# RelayModule_LED.net
KiCad netlist of a schematic drawn in Altium Designer
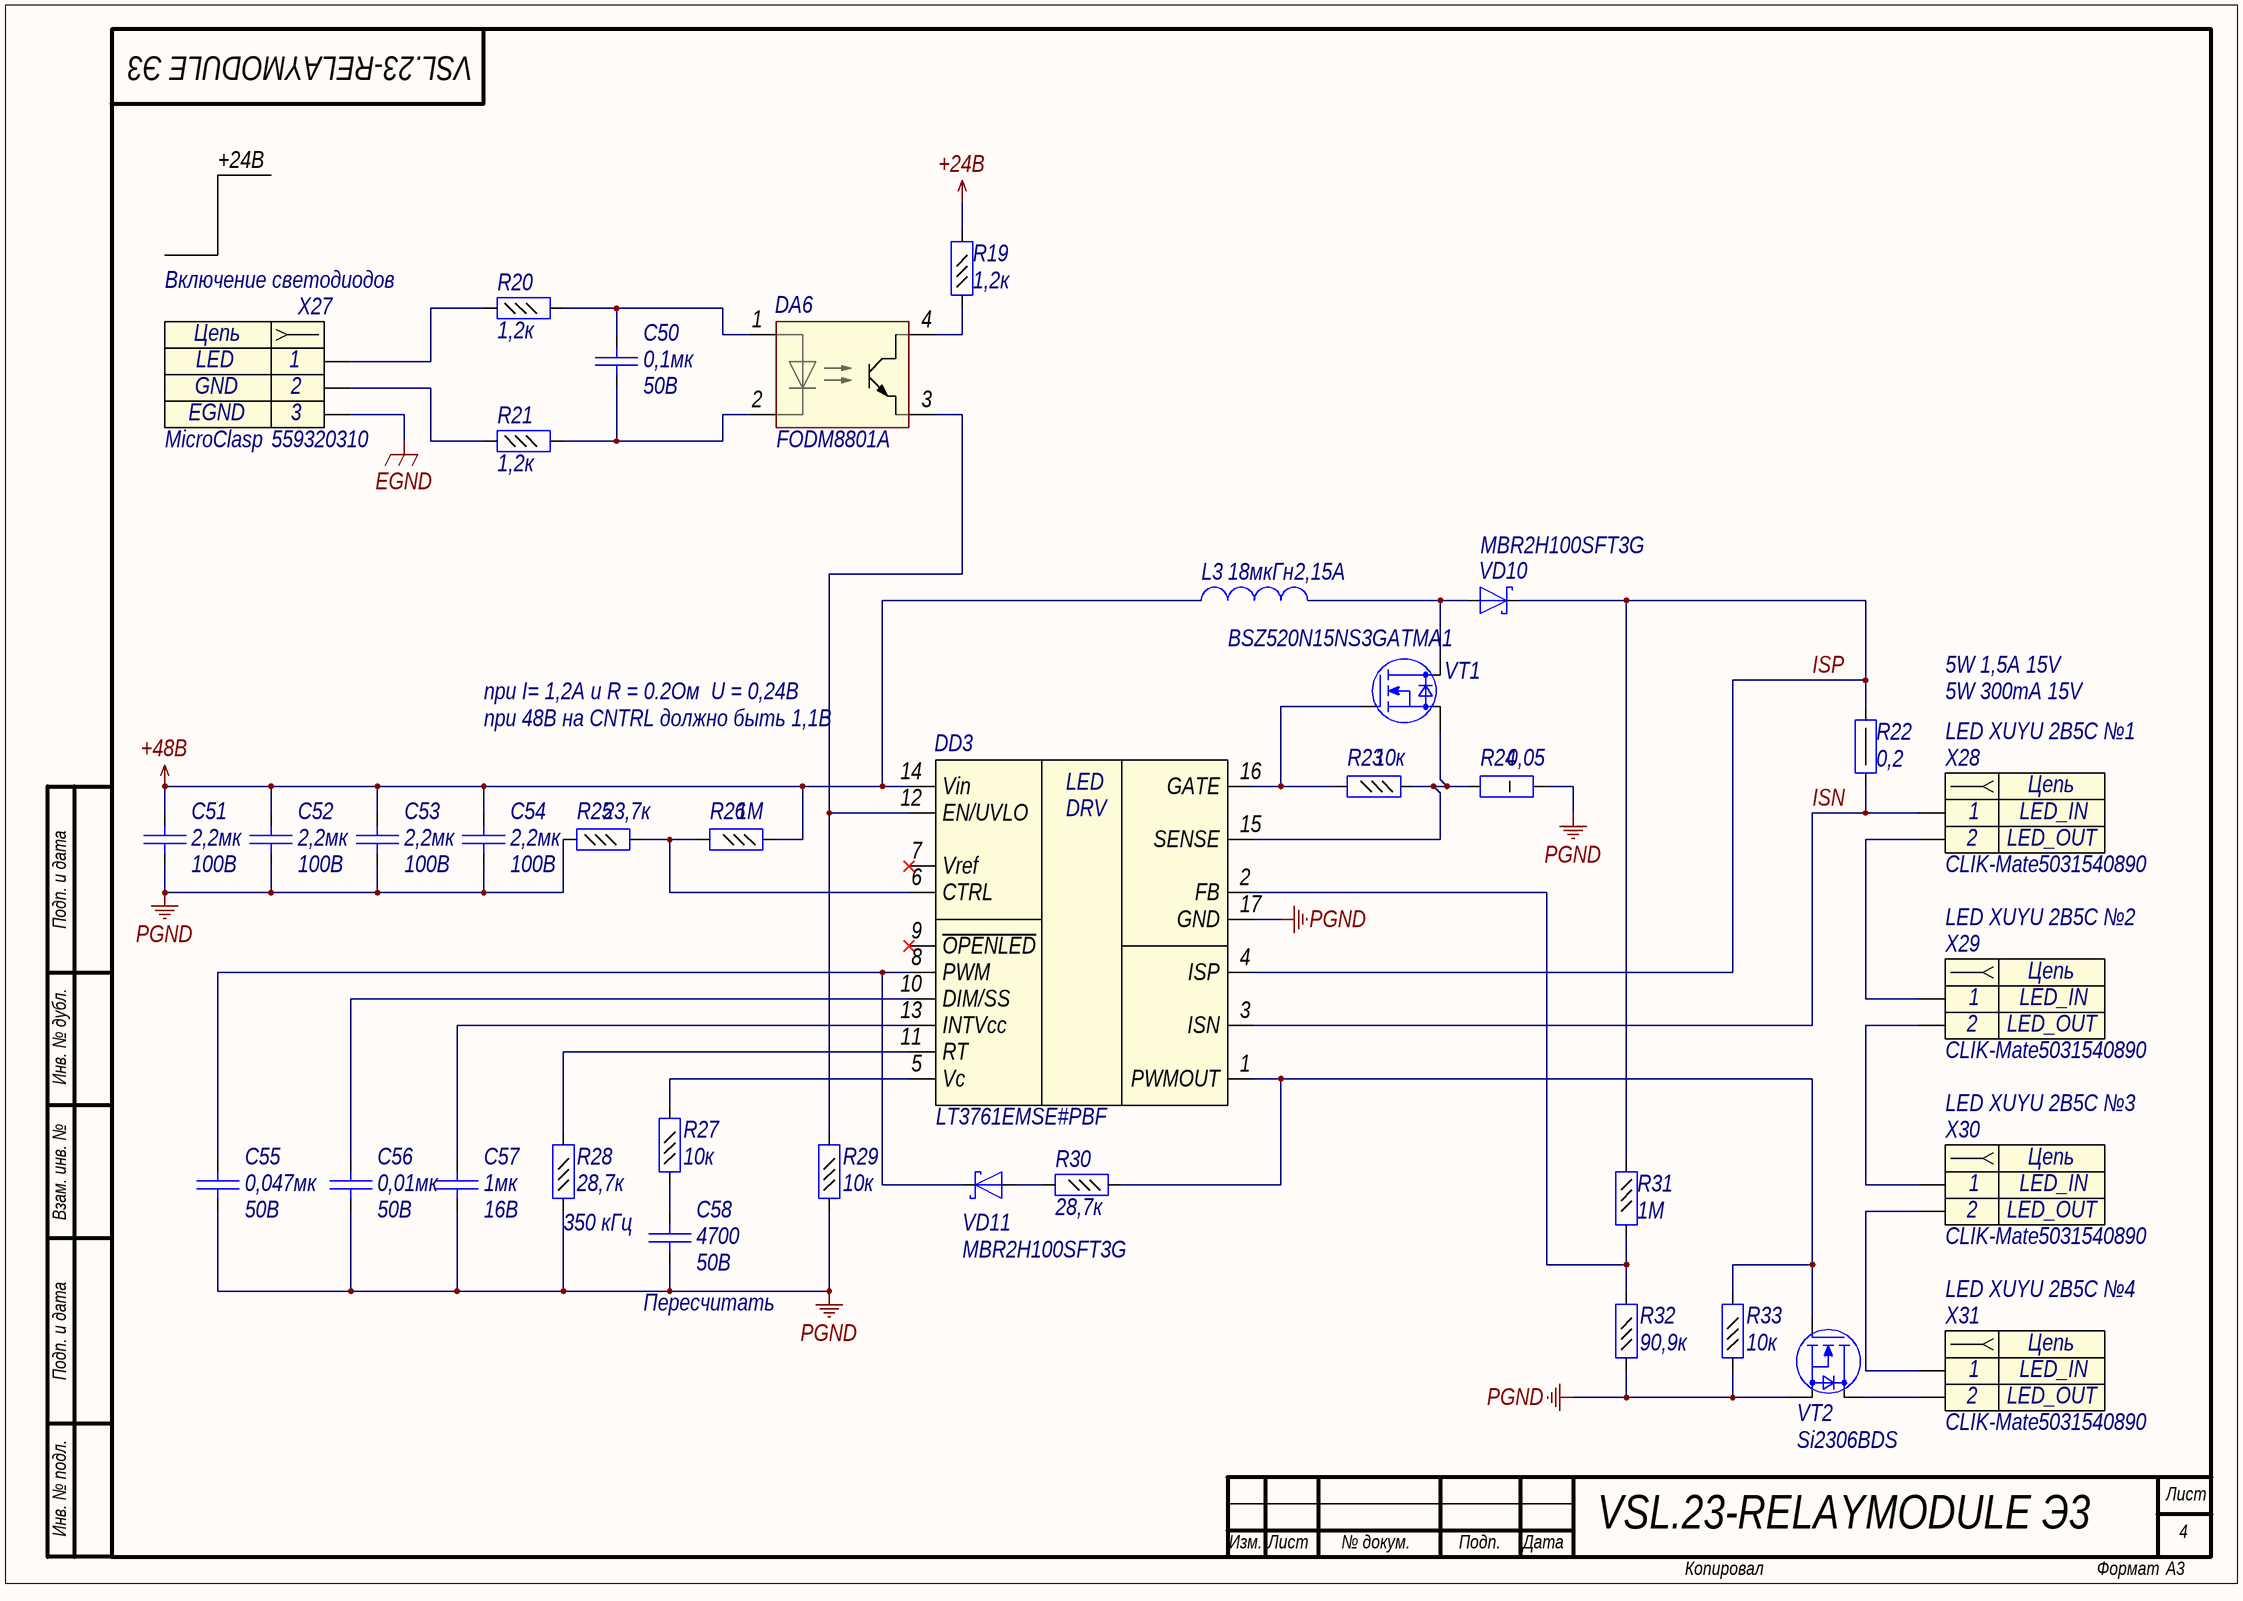
[diagram p0: RelayModule_LED.SchDoc]

(export (version "E")
  (design (tool "Eeschema 10.0.6"))
  (components
    (comp (ref "C50")
      (value "0,1мк")
      (footprint "C0402")
      (description "Конденсатор")
      (fields (field (name "VOLTAGE") "50В") (field (name "PART NUMBER") "GRM155R71H104KE14D "))
      (libsource (lib "MOP44") (part "Capacitor"))
    )
    (comp (ref "C51")
      (value "2,2мк")
      (footprint "C1812")
      (description "Конденсатор")
      (fields (field (name "VOLTAGE") "100В") (field (name "PART NUMBER") "C4532X7R2A225M"))
      (libsource (lib "MOP44") (part "Capacitor"))
    )
    (comp (ref "C52")
      (value "2,2мк")
      (footprint "C1812")
      (description "Конденсатор")
      (fields (field (name "VOLTAGE") "100В") (field (name "PART NUMBER") "C4532X7R2A225M"))
      (libsource (lib "MOP44") (part "Capacitor"))
    )
    (comp (ref "C53")
      (value "2,2мк")
      (footprint "C1812")
      (description "Конденсатор")
      (fields (field (name "VOLTAGE") "100В") (field (name "PART NUMBER") "C4532X7R2A225M"))
      (libsource (lib "MOP44") (part "Capacitor"))
    )
    (comp (ref "C54")
      (value "2,2мк")
      (footprint "C1812")
      (description "Конденсатор")
      (fields (field (name "VOLTAGE") "100В") (field (name "PART NUMBER") "C4532X7R2A225M"))
      (libsource (lib "MOP44") (part "Capacitor"))
    )
    (comp (ref "C55")
      (value "0,047мк")
      (footprint "C0402")
      (description "Конденсатор")
      (fields (field (name "VOLTAGE") "50В") (field (name "PART NUMBER") "CC0402KRX7R9BB473"))
      (libsource (lib "MOP44") (part "Capacitor"))
    )
    (comp (ref "C56")
      (value "0,01мк")
      (footprint "C0402")
      (description "Конденсатор")
      (fields (field (name "VOLTAGE") "50B") (field (name "PART NUMBER") "GRM155R71H103K"))
      (libsource (lib "MOP44") (part "Capacitor"))
    )
    (comp (ref "C57")
      (value "1мк")
      (footprint "C0603")
      (description "Конденсатор")
      (fields
        (field (name "VOLTAGE") "16B")
        (field (name "PART NUMBER") "GRM188R71C105KA12D**")
        (field (name "Comment") "Capacitor")
      )
      (libsource (lib "MOP44") (part "Capacitor"))
    )
    (comp (ref "C58")
      (value "4700")
      (footprint "C0402")
      (description "Конденсатор")
      (fields (field (name "VOLTAGE") "50B") (field (name "PART NUMBER") "GRM155R71H472K"))
      (libsource (lib "MOP44") (part "Capacitor"))
    )
    (comp (ref "DA6")
      (value "OPTO-1")
      (footprint "Miniflat4")
      (description "Опторазвязка")
      (fields (field (name "PART NUMBER") "FODM8801A") (field (name "MANUFACTURER") "ON Semiconductor"))
      (libsource (lib "MOP44") (part "OPTO-1"))
    )
    (comp (ref "DD3")
      (value "LT3761")
      (footprint "MSOP16")
      (description "LED Controller with  Internal PWM Generato")
      (fields (field (name "PART NUMBER") "LT3761EMSE#PBF"))
      (libsource (lib "MOP44") (part "LT3761"))
    )
    (comp (ref "L3")
      (value "18мкГн")
      (footprint "SDR1006")
      (description "EMI Suppression Filter")
      (fields
        (field (name "RATED CURRENT") "2,15A")
        (field (name "PART NUMBER") "SDR1006- 180ML")
        (field (name "Comment") "Inductor")
      )
      (libsource (lib "MOP44") (part "Inductor"))
    )
    (comp (ref "R19")
      (value "1,2к")
      (footprint "R0402")
      (description "Резистор")
      (fields (field (name "PART NUMBER") "RC0402FR-071K2") (field (name "POWER") "0,062Вт"))
      (libsource (lib "") (part "Resistor_0,062Вт_1"))
    )
    (comp (ref "R20")
      (value "1,2к")
      (footprint "R0402")
      (description "Резистор")
      (fields (field (name "PART NUMBER") "RC0402FR-071K2") (field (name "POWER") "0,062Вт"))
      (libsource (lib "") (part "Resistor_0,062Вт_3"))
    )
    (comp (ref "R21")
      (value "1,2к")
      (footprint "R0402")
      (description "Резистор")
      (fields (field (name "PART NUMBER") "RC0402FR-071K2") (field (name "POWER") "0,062Вт"))
      (libsource (lib "") (part "Resistor_0,062Вт_3"))
    )
    (comp (ref "R22")
      (value "0,2")
      (footprint "R1210")
      (description "Резистор")
      (fields (field (name "PART NUMBER") "RL1210FR-070R2L") (field (name "POWER") "0,5Вт"))
      (libsource (lib "MOP44") (part "Resistor_0,5Вт"))
    )
    (comp (ref "R23")
      (value "10к")
      (footprint "R0402")
      (description "Резистор")
      (fields (field (name "PART NUMBER") "RC0402FR-0710KL") (field (name "POWER") "0,062Вт"))
      (libsource (lib "") (part "Resistor_0,062Вт_2"))
    )
    (comp (ref "R24")
      (value "0,05")
      (footprint "R2010")
      (description "Резистор")
      (fields (field (name "PART NUMBER") "RL2010FK-070R05L") (field (name "POWER") "0,75Вт"))
      (libsource (lib "MOP44") (part "Resistor_1Вт"))
    )
    (comp (ref "R25")
      (value "23,7к")
      (footprint "R0402")
      (description "Резистор")
      (fields (field (name "PART NUMBER") "RC0402FR-0723K7L") (field (name "POWER") "0,062Вт"))
      (libsource (lib "") (part "Resistor_0,062Вт_3"))
    )
    (comp (ref "R26")
      (value "1М")
      (footprint "R0402")
      (description "Резистор")
      (fields (field (name "PART NUMBER") "RC0402FR-071ML") (field (name "POWER") "0,062Вт"))
      (libsource (lib "") (part "Resistor_0,062Вт_2"))
    )
    (comp (ref "R27")
      (value "10к")
      (footprint "R0402")
      (description "Резистор")
      (fields (field (name "PART NUMBER") "RC0402FR-0710KL") (field (name "POWER") "0,062Вт"))
      (libsource (lib "") (part "Resistor_0,062Вт_1"))
    )
    (comp (ref "R28")
      (value "28,7к")
      (footprint "R0402")
      (description "Резистор")
      (fields (field (name "PART NUMBER") "RC0402FR-0728K7L") (field (name "POWER") "0,062Вт"))
      (libsource (lib "") (part "Resistor_0,062Вт_1"))
    )
    (comp (ref "R29")
      (value "10к")
      (footprint "R0402")
      (description "Резистор")
      (fields (field (name "PART NUMBER") "RC0402FR-0710KL") (field (name "POWER") "0,062Вт"))
      (libsource (lib "") (part "Resistor_0,062Вт_1"))
    )
    (comp (ref "R30")
      (value "28,7к")
      (footprint "R0402")
      (description "Резистор")
      (fields (field (name "PART NUMBER") "RC0402FR-0728K7L") (field (name "POWER") "0,062Вт"))
      (libsource (lib "") (part "Resistor_0,062Вт_2"))
    )
    (comp (ref "R31")
      (value "1М")
      (footprint "R0402")
      (description "Резистор")
      (fields (field (name "PART NUMBER") "RC0402FR-071ML") (field (name "POWER") "0,062Вт"))
      (libsource (lib "MOP44") (part "Resistor_0,062Вт"))
    )
    (comp (ref "R32")
      (value "90,9к")
      (footprint "R0402")
      (description "Резистор")
      (fields (field (name "PART NUMBER") "RC0402FR-0790K9L") (field (name "POWER") "0,062Вт"))
      (libsource (lib "") (part "Resistor_0,062Вт_1"))
    )
    (comp (ref "R33")
      (value "10к")
      (footprint "R0402")
      (description "Резистор")
      (fields (field (name "PART NUMBER") "RC0402FR-0710KL") (field (name "POWER") "0,062Вт"))
      (libsource (lib "") (part "Resistor_0,062Вт_1"))
    )
    (comp (ref "VD10")
      (value "DiodeSchottky")
      (footprint "SOD-123")
      (description "Диод Шоттки")
      (fields (field (name "PART NUMBER") "MBR2H100SFT3G"))
      (libsource (lib "MOP44") (part "DiodeSchottky"))
    )
    (comp (ref "VD11")
      (value "DiodeSchottky")
      (footprint "SOD-123")
      (description "Диод Шоттки")
      (fields (field (name "PART NUMBER") "MBR2H100SFT3G"))
      (libsource (lib "MOP44") (part "DiodeSchottky"))
    )
    (comp (ref "VT1")
      (value "N-MOSFET")
      (footprint "TSDSON8")
      (fields
        (field (name "PART NUMBER") "BSZ520N15NS3GATMA1")
        (field (name "MANUFACTURER") "Infineon Technologies")
      )
      (libsource (lib "MOP44") (part "N-MOSFET"))
    )
    (comp (ref "VT2")
      (value "N-MOSFET")
      (footprint "SOT23-3")
      (fields (field (name "PART NUMBER") "Si2306BDS") (field (name "MANUFACTURER") "Vishay"))
      (libsource (lib "MOP44") (part "N-MOSFET"))
    )
    (comp (ref "X27")
      (value "Включение светодиодов")
      (footprint "MOLEX_559320310")
      (description "Разъем - 3 конт. розетка")
      (fields (field (name "PART NAME") "MicroClasp") (field (name "PART NUMBER") "559320310"))
      (libsource (lib "MOP44") (part "Header_3_sct"))
    )
    (comp (ref "X28")
      (value "LED XUYU 2B5C №1")
      (footprint "MOLEX_5031540890")
      (description "Разъем - 2 конт. розетка")
      (fields (field (name "PART NAME") "CLIK-Mate") (field (name "PART NUMBER") "5031540890"))
      (libsource (lib "MOP44") (part "Header_2_sct"))
    )
    (comp (ref "X29")
      (value "LED XUYU 2B5C №2")
      (footprint "MOLEX_5031540890")
      (description "Разъем - 2 конт. розетка")
      (fields (field (name "PART NAME") "CLIK-Mate") (field (name "PART NUMBER") "5031540890"))
      (libsource (lib "MOP44") (part "Header_2_sct"))
    )
    (comp (ref "X30")
      (value "LED XUYU 2B5C №3")
      (footprint "MOLEX_5031540890")
      (description "Разъем - 2 конт. розетка")
      (fields (field (name "PART NAME") "CLIK-Mate") (field (name "PART NUMBER") "5031540890"))
      (libsource (lib "MOP44") (part "Header_2_sct"))
    )
    (comp (ref "X31")
      (value "LED XUYU 2B5C №4")
      (footprint "MOLEX_5031540890")
      (description "Разъем - 2 конт. розетка")
      (fields (field (name "PART NAME") "CLIK-Mate") (field (name "PART NUMBER") "5031540890"))
      (libsource (lib "MOP44") (part "Header_2_sct"))
    )
  )
  (nets
    (net (code "1") (name "+24B") (class "Default")
      (node (ref "R19") (pin "2") (pinfunction "2_2") (pintype "passive"))
    )
    (net (code "2") (name "+48B") (class "Default")
      (node (ref "C51") (pin "2") (pinfunction "2_2") (pintype "passive"))
      (node (ref "C52") (pin "2") (pinfunction "2_2") (pintype "passive"))
      (node (ref "C53") (pin "2") (pinfunction "2_2") (pintype "passive"))
      (node (ref "C54") (pin "2") (pinfunction "2_2") (pintype "passive"))
      (node (ref "DD3") (pin "14") (pinfunction "Vin_14") (pintype "passive"))
      (node (ref "L3") (pin "1") (pinfunction "1_1") (pintype "passive"))
      (node (ref "R26") (pin "1") (pinfunction "1_1") (pintype "passive"))
    )
    (net (code "3") (name "/ISN") (class "Default")
      (node (ref "DD3") (pin "3") (pinfunction "ISN_3") (pintype "passive"))
      (node (ref "R22") (pin "2") (pinfunction "2_2") (pintype "passive"))
      (node (ref "X28") (pin "1") (pinfunction "1_1") (pintype "passive"))
    )
    (net (code "4") (name "/ISP") (class "Default")
      (node (ref "DD3") (pin "4") (pinfunction "ISP_4") (pintype "passive"))
      (node (ref "R22") (pin "1") (pinfunction "1_1") (pintype "passive"))
      (node (ref "R31") (pin "1") (pinfunction "1_1") (pintype "passive"))
      (node (ref "VD10") (pin "1") (pinfunction "K_1") (pintype "passive"))
    )
    (net (code "5") (name "EGND") (class "Default")
      (node (ref "X27") (pin "3") (pinfunction "3_3") (pintype "passive"))
    )
    (net (code "6") (name "Net-(C50-Pad1)") (class "Default")
      (node (ref "C50") (pin "1") (pinfunction "1_1") (pintype "passive"))
      (node (ref "DA6") (pin "2") (pintype "passive"))
      (node (ref "R21") (pin "2") (pinfunction "2_2") (pintype "passive"))
    )
    (net (code "7") (name "Net-(C50-Pad2)") (class "Default")
      (node (ref "C50") (pin "2") (pinfunction "2_2") (pintype "passive"))
      (node (ref "DA6") (pin "1") (pintype "passive"))
      (node (ref "R20") (pin "2") (pinfunction "2_2") (pintype "passive"))
    )
    (net (code "8") (name "Net-(C58-Pad2)") (class "Default")
      (node (ref "C58") (pin "2") (pinfunction "2_2") (pintype "passive"))
      (node (ref "R27") (pin "1") (pinfunction "1_1") (pintype "passive"))
    )
    (net (code "9") (name "Net-(DA6-Pad4)") (class "Default")
      (node (ref "DA6") (pin "4") (pintype "passive"))
      (node (ref "R19") (pin "1") (pinfunction "1_1") (pintype "passive"))
    )
    (net (code "10") (name "Net-(DD3-CTRL)") (class "Default")
      (node (ref "DD3") (pin "6") (pinfunction "CTRL_6") (pintype "passive"))
      (node (ref "R25") (pin "2") (pinfunction "2_2") (pintype "passive"))
      (node (ref "R26") (pin "2") (pinfunction "2_2") (pintype "passive"))
    )
    (net (code "11") (name "Net-(DD3-DIM{slash}SS)") (class "Default")
      (node (ref "C56") (pin "2") (pinfunction "2_2") (pintype "passive"))
      (node (ref "DD3") (pin "10") (pinfunction "DIM/SS_10") (pintype "passive"))
    )
    (net (code "12") (name "Net-(DD3-EN{slash}UVLO)") (class "Default")
      (node (ref "DA6") (pin "3") (pintype "passive"))
      (node (ref "DD3") (pin "12") (pinfunction "EN/UVLO_12") (pintype "passive"))
      (node (ref "R29") (pin "2") (pinfunction "2_2") (pintype "passive"))
    )
    (net (code "13") (name "Net-(DD3-FB)") (class "Default")
      (node (ref "DD3") (pin "2") (pinfunction "FB_2") (pintype "passive"))
      (node (ref "R31") (pin "2") (pinfunction "2_2") (pintype "passive"))
      (node (ref "R32") (pin "2") (pinfunction "2_2") (pintype "passive"))
    )
    (net (code "14") (name "Net-(DD3-GATE)") (class "Default")
      (node (ref "DD3") (pin "16") (pinfunction "GATE_16") (pintype "passive"))
      (node (ref "R23") (pin "2") (pinfunction "2_2") (pintype "passive"))
      (node (ref "VT1") (pin "1") (pinfunction "G_1") (pintype "passive"))
    )
    (net (code "15") (name "Net-(DD3-INTVcc)") (class "Default")
      (node (ref "C57") (pin "2") (pinfunction "2_2") (pintype "passive"))
      (node (ref "DD3") (pin "13") (pinfunction "INTVcc_13") (pintype "passive"))
    )
    (net (code "16") (name "Net-(DD3-PWM)") (class "Default")
      (node (ref "C55") (pin "2") (pinfunction "2_2") (pintype "passive"))
      (node (ref "DD3") (pin "8") (pinfunction "PWM_8") (pintype "passive"))
      (node (ref "VD11") (pin "1") (pinfunction "K_1") (pintype "passive"))
    )
    (net (code "17") (name "Net-(DD3-PWMOUT)") (class "Default")
      (node (ref "DD3") (pin "1") (pinfunction "PWMOUT_1") (pintype "passive"))
      (node (ref "R30") (pin "1") (pinfunction "1_1") (pintype "passive"))
      (node (ref "R33") (pin "2") (pinfunction "2_2") (pintype "passive"))
      (node (ref "VT2") (pin "1") (pinfunction "G_1") (pintype "passive"))
    )
    (net (code "18") (name "Net-(DD3-RT)") (class "Default")
      (node (ref "DD3") (pin "11") (pinfunction "RT_11") (pintype "passive"))
      (node (ref "R28") (pin "2") (pinfunction "2_2") (pintype "passive"))
    )
    (net (code "19") (name "Net-(DD3-SENSE)") (class "Default")
      (node (ref "DD3") (pin "15") (pinfunction "SENSE_15") (pintype "passive"))
      (node (ref "R23") (pin "1") (pinfunction "1_1") (pintype "passive"))
      (node (ref "R24") (pin "1") (pinfunction "1_1") (pintype "passive"))
      (node (ref "VT1") (pin "3") (pinfunction "S_3") (pintype "passive"))
    )
    (net (code "20") (name "Net-(DD3-Vc)") (class "Default")
      (node (ref "DD3") (pin "5") (pinfunction "Vc_5") (pintype "passive"))
      (node (ref "R27") (pin "2") (pinfunction "2_2") (pintype "passive"))
    )
    (net (code "21") (name "Net-(R20-Pad1)") (class "Default")
      (node (ref "R20") (pin "1") (pinfunction "1_1") (pintype "passive"))
      (node (ref "X27") (pin "1") (pinfunction "1_1") (pintype "passive"))
    )
    (net (code "22") (name "Net-(R21-Pad1)") (class "Default")
      (node (ref "R21") (pin "1") (pinfunction "1_1") (pintype "passive"))
      (node (ref "X27") (pin "2") (pinfunction "2_2") (pintype "passive"))
    )
    (net (code "23") (name "Net-(VD10-A)") (class "Default")
      (node (ref "L3") (pin "2") (pinfunction "2_2") (pintype "passive"))
      (node (ref "VD10") (pin "2") (pinfunction "A_2") (pintype "passive"))
      (node (ref "VT1") (pin "2") (pinfunction "D_2") (pintype "passive"))
    )
    (net (code "24") (name "Net-(VD11-A)") (class "Default")
      (node (ref "R30") (pin "2") (pinfunction "2_2") (pintype "passive"))
      (node (ref "VD11") (pin "2") (pinfunction "A_2") (pintype "passive"))
    )
    (net (code "25") (name "Net-(VT2-D)") (class "Default")
      (node (ref "VT2") (pin "2") (pinfunction "D_2") (pintype "passive"))
      (node (ref "X31") (pin "2") (pinfunction "2_2") (pintype "passive"))
    )
    (net (code "26") (name "Net-(X28-Pad2)") (class "Default")
      (node (ref "X28") (pin "2") (pinfunction "2_2") (pintype "passive"))
      (node (ref "X29") (pin "1") (pinfunction "1_1") (pintype "passive"))
    )
    (net (code "27") (name "Net-(X29-Pad2)") (class "Default")
      (node (ref "X29") (pin "2") (pinfunction "2_2") (pintype "passive"))
      (node (ref "X30") (pin "1") (pinfunction "1_1") (pintype "passive"))
    )
    (net (code "28") (name "Net-(X30-Pad2)") (class "Default")
      (node (ref "X30") (pin "2") (pinfunction "2_2") (pintype "passive"))
      (node (ref "X31") (pin "1") (pinfunction "1_1") (pintype "passive"))
    )
    (net (code "29") (name "PGND") (class "Default")
      (node (ref "C51") (pin "1") (pinfunction "1_1") (pintype "passive"))
      (node (ref "C52") (pin "1") (pinfunction "1_1") (pintype "passive"))
      (node (ref "C53") (pin "1") (pinfunction "1_1") (pintype "passive"))
      (node (ref "C54") (pin "1") (pinfunction "1_1") (pintype "passive"))
      (node (ref "C55") (pin "1") (pinfunction "1_1") (pintype "passive"))
      (node (ref "C56") (pin "1") (pinfunction "1_1") (pintype "passive"))
      (node (ref "C57") (pin "1") (pinfunction "1_1") (pintype "passive"))
      (node (ref "C58") (pin "1") (pinfunction "1_1") (pintype "passive"))
      (node (ref "DD3") (pin "17") (pinfunction "GND_17") (pintype "passive"))
      (node (ref "R24") (pin "2") (pinfunction "5_2") (pintype "passive"))
      (node (ref "R25") (pin "1") (pinfunction "1_1") (pintype "passive"))
      (node (ref "R28") (pin "1") (pinfunction "1_1") (pintype "passive"))
      (node (ref "R29") (pin "1") (pinfunction "1_1") (pintype "passive"))
      (node (ref "R32") (pin "1") (pinfunction "1_1") (pintype "passive"))
      (node (ref "R33") (pin "1") (pinfunction "1_1") (pintype "passive"))
      (node (ref "VT2") (pin "3") (pinfunction "S_3") (pintype "passive"))
    )
    (net (code "30") (name "unconnected-(DD3-Vref-Pad7)") (class "Default")
      (node (ref "DD3") (pin "7") (pinfunction "Vref_7") (pintype "passive+no_connect"))
    )
    (net (code "31") (name "unconnected-(DD3-~{OPENLED}-Pad9)") (class "Default")
      (node (ref "DD3") (pin "9") (pinfunction "~{OPENLED}_9") (pintype "passive+no_connect"))
    )
  )
)
